# relay-set-d-decode.net
KiCad netlist of a schematic drawn in EAGLE
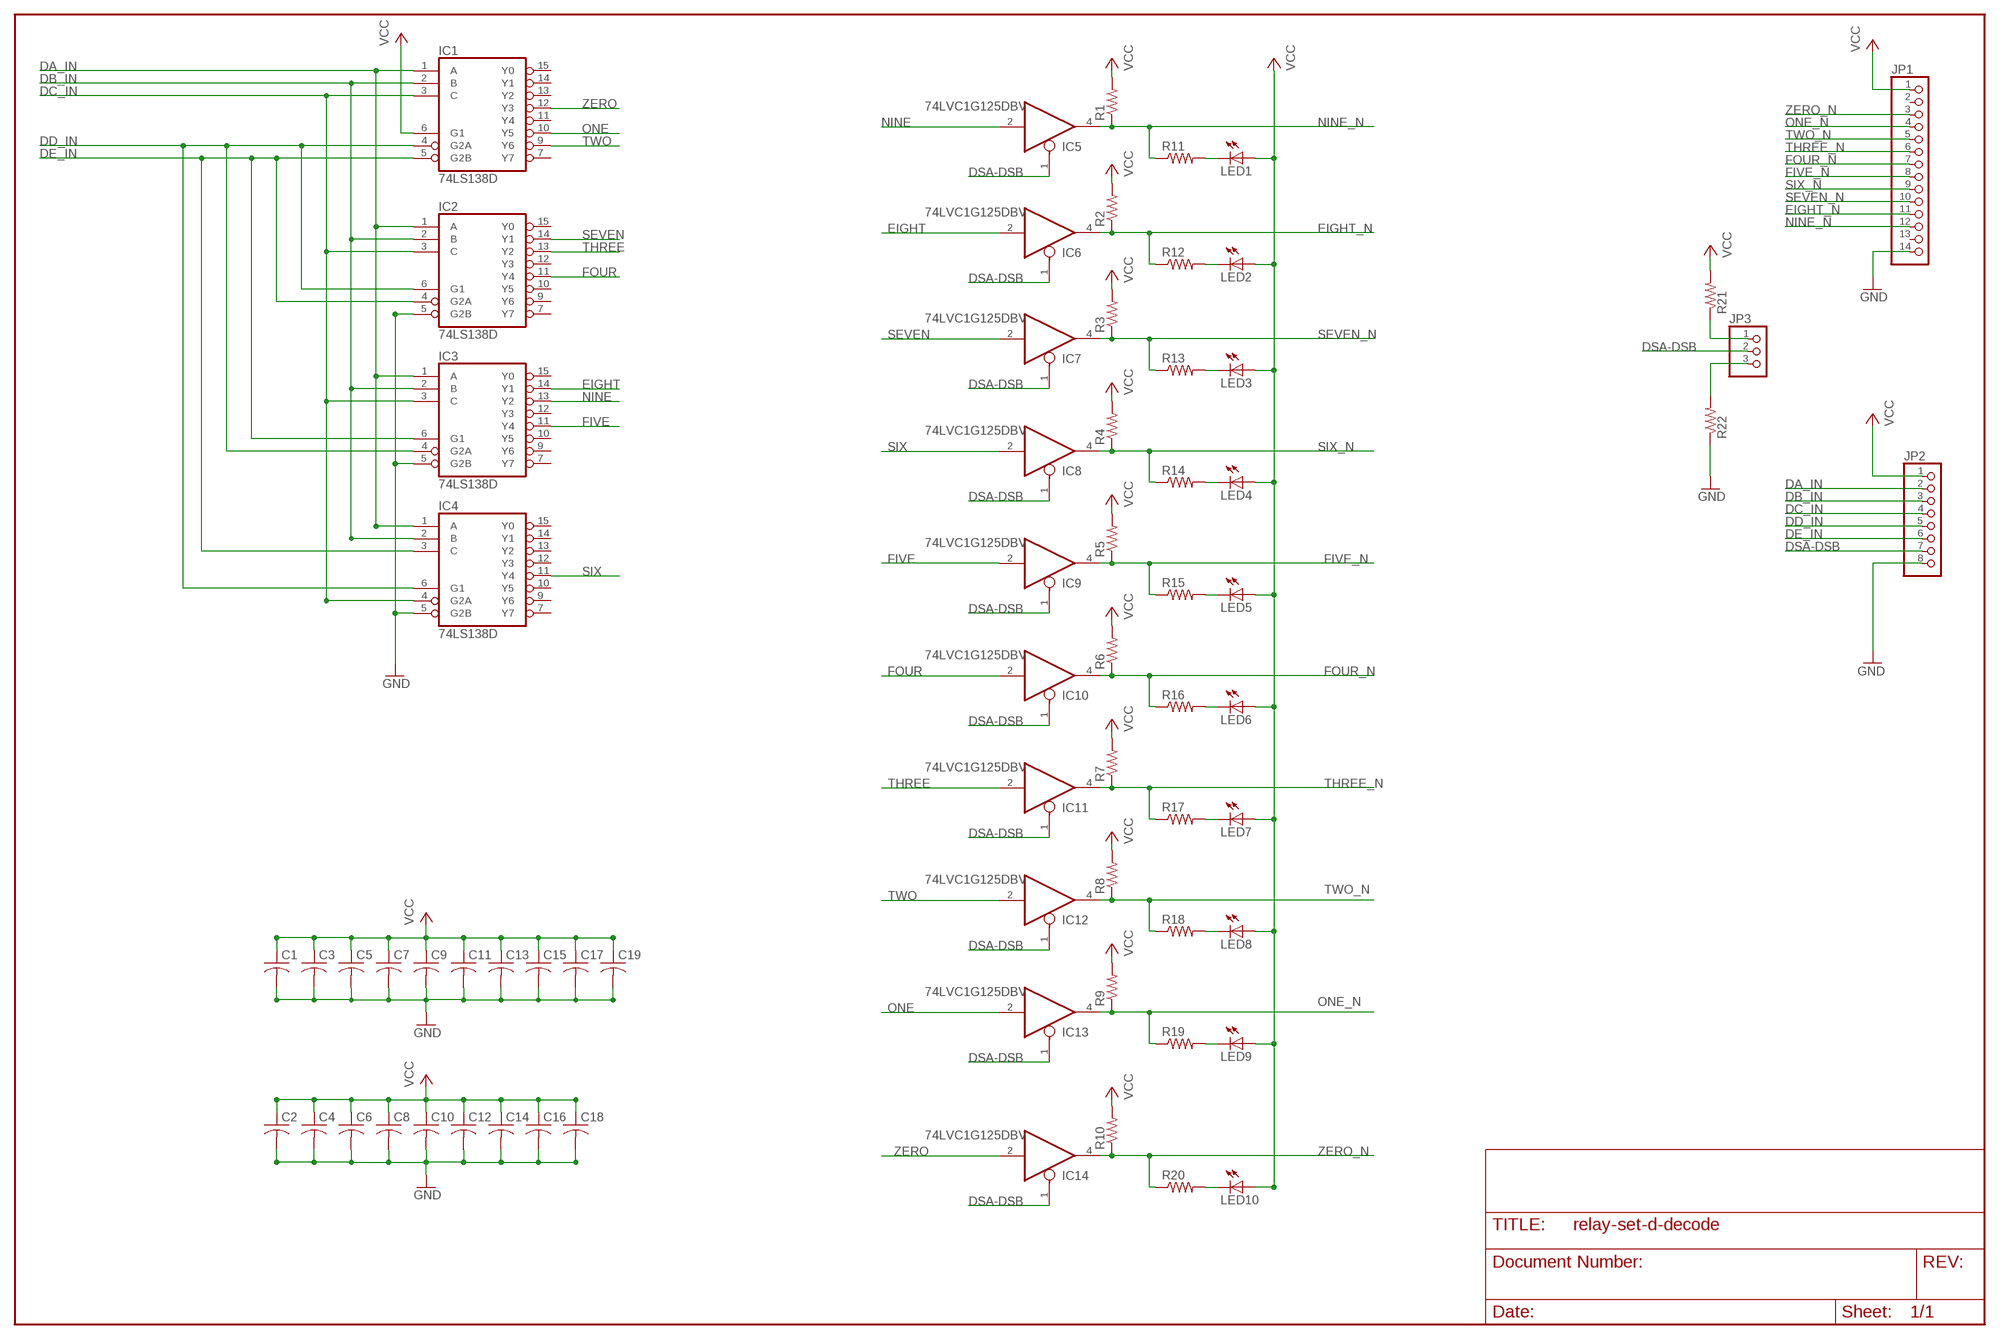
[diagram p0: schematic, sheet 1]

(export (version "E")
  (design (tool "Eeschema 10.0.6"))
  (components
    (comp (ref "C1")
      (value "C-USC0805")
      (footprint "eagle-import:C0805")
      (libsource (lib "eagle-import") (part "C-USC0805"))
    )
    (comp (ref "C2")
      (value "C-USC0805")
      (footprint "eagle-import:C0805")
      (libsource (lib "eagle-import") (part "C-USC0805"))
    )
    (comp (ref "C3")
      (value "C-USC0805")
      (footprint "eagle-import:C0805")
      (libsource (lib "eagle-import") (part "C-USC0805"))
    )
    (comp (ref "C4")
      (value "C-USC0805")
      (footprint "eagle-import:C0805")
      (libsource (lib "eagle-import") (part "C-USC0805"))
    )
    (comp (ref "C5")
      (value "C-USC0805")
      (footprint "eagle-import:C0805")
      (libsource (lib "eagle-import") (part "C-USC0805"))
    )
    (comp (ref "C6")
      (value "C-USC0805")
      (footprint "eagle-import:C0805")
      (libsource (lib "eagle-import") (part "C-USC0805"))
    )
    (comp (ref "C7")
      (value "C-USC0805")
      (footprint "eagle-import:C0805")
      (libsource (lib "eagle-import") (part "C-USC0805"))
    )
    (comp (ref "C8")
      (value "C-USC0805")
      (footprint "eagle-import:C0805")
      (libsource (lib "eagle-import") (part "C-USC0805"))
    )
    (comp (ref "C9")
      (value "C-USC0805")
      (footprint "eagle-import:C0805")
      (libsource (lib "eagle-import") (part "C-USC0805"))
    )
    (comp (ref "C10")
      (value "C-USC0805")
      (footprint "eagle-import:C0805")
      (libsource (lib "eagle-import") (part "C-USC0805"))
    )
    (comp (ref "C11")
      (value "C-USC0805")
      (footprint "eagle-import:C0805")
      (libsource (lib "eagle-import") (part "C-USC0805"))
    )
    (comp (ref "C12")
      (value "C-USC0805")
      (footprint "eagle-import:C0805")
      (libsource (lib "eagle-import") (part "C-USC0805"))
    )
    (comp (ref "C13")
      (value "C-USC0805")
      (footprint "eagle-import:C0805")
      (libsource (lib "eagle-import") (part "C-USC0805"))
    )
    (comp (ref "C14")
      (value "C-USC0805")
      (footprint "eagle-import:C0805")
      (libsource (lib "eagle-import") (part "C-USC0805"))
    )
    (comp (ref "C15")
      (value "C-USC0805")
      (footprint "eagle-import:C0805")
      (libsource (lib "eagle-import") (part "C-USC0805"))
    )
    (comp (ref "C16")
      (value "C-USC0805")
      (footprint "eagle-import:C0805")
      (libsource (lib "eagle-import") (part "C-USC0805"))
    )
    (comp (ref "C17")
      (value "C-USC0805")
      (footprint "eagle-import:C0805")
      (libsource (lib "eagle-import") (part "C-USC0805"))
    )
    (comp (ref "C18")
      (value "C-USC0805")
      (footprint "eagle-import:C0805")
      (libsource (lib "eagle-import") (part "C-USC0805"))
    )
    (comp (ref "C19")
      (value "C-USC0805")
      (footprint "eagle-import:C0805")
      (libsource (lib "eagle-import") (part "C-USC0805"))
    )
    (comp (ref "IC1")
      (value "74LS138D")
      (footprint "eagle-import:SO16")
      (libsource (lib "eagle-import") (part "74138DLS"))
    )
    (comp (ref "IC2")
      (value "74LS138D")
      (footprint "eagle-import:SO16")
      (libsource (lib "eagle-import") (part "74138DLS"))
    )
    (comp (ref "IC3")
      (value "74LS138D")
      (footprint "eagle-import:SO16")
      (libsource (lib "eagle-import") (part "74138DLS"))
    )
    (comp (ref "IC4")
      (value "74LS138D")
      (footprint "eagle-import:SO16")
      (libsource (lib "eagle-import") (part "74138DLS"))
    )
    (comp (ref "IC5")
      (value "74LVC1G125DBV")
      (footprint "eagle-import:SOT23-5")
      (libsource (lib "eagle-import") (part "741G125DBVLVC"))
    )
    (comp (ref "IC6")
      (value "74LVC1G125DBV")
      (footprint "eagle-import:SOT23-5")
      (libsource (lib "eagle-import") (part "741G125DBVLVC"))
    )
    (comp (ref "IC7")
      (value "74LVC1G125DBV")
      (footprint "eagle-import:SOT23-5")
      (libsource (lib "eagle-import") (part "741G125DBVLVC"))
    )
    (comp (ref "IC8")
      (value "74LVC1G125DBV")
      (footprint "eagle-import:SOT23-5")
      (libsource (lib "eagle-import") (part "741G125DBVLVC"))
    )
    (comp (ref "IC9")
      (value "74LVC1G125DBV")
      (footprint "eagle-import:SOT23-5")
      (libsource (lib "eagle-import") (part "741G125DBVLVC"))
    )
    (comp (ref "IC10")
      (value "74LVC1G125DBV")
      (footprint "eagle-import:SOT23-5")
      (libsource (lib "eagle-import") (part "741G125DBVLVC"))
    )
    (comp (ref "IC11")
      (value "74LVC1G125DBV")
      (footprint "eagle-import:SOT23-5")
      (libsource (lib "eagle-import") (part "741G125DBVLVC"))
    )
    (comp (ref "IC12")
      (value "74LVC1G125DBV")
      (footprint "eagle-import:SOT23-5")
      (libsource (lib "eagle-import") (part "741G125DBVLVC"))
    )
    (comp (ref "IC13")
      (value "74LVC1G125DBV")
      (footprint "eagle-import:SOT23-5")
      (libsource (lib "eagle-import") (part "741G125DBVLVC"))
    )
    (comp (ref "IC14")
      (value "74LVC1G125DBV")
      (footprint "eagle-import:SOT23-5")
      (libsource (lib "eagle-import") (part "741G125DBVLVC"))
    )
    (comp (ref "JP1")
      (value "PINHD-1X14")
      (footprint "eagle-import:1X14")
      (libsource (lib "eagle-import") (part "PINHD-1X14"))
    )
    (comp (ref "JP2")
      (value "PINHD-1X8")
      (footprint "eagle-import:1X08")
      (libsource (lib "eagle-import") (part "PINHD-1X8"))
    )
    (comp (ref "JP3")
      (value "PINHD-1X3")
      (footprint "eagle-import:1X03")
      (libsource (lib "eagle-import") (part "PINHD-1X3"))
    )
    (comp (ref "LED1")
      (value "LEDCHIP-LED0805")
      (footprint "eagle-import:CHIP-LED0805")
      (libsource (lib "eagle-import") (part "LEDCHIP-LED0805"))
    )
    (comp (ref "LED2")
      (value "LEDCHIP-LED0805")
      (footprint "eagle-import:CHIP-LED0805")
      (libsource (lib "eagle-import") (part "LEDCHIP-LED0805"))
    )
    (comp (ref "LED3")
      (value "LEDCHIP-LED0805")
      (footprint "eagle-import:CHIP-LED0805")
      (libsource (lib "eagle-import") (part "LEDCHIP-LED0805"))
    )
    (comp (ref "LED4")
      (value "LEDCHIP-LED0805")
      (footprint "eagle-import:CHIP-LED0805")
      (libsource (lib "eagle-import") (part "LEDCHIP-LED0805"))
    )
    (comp (ref "LED5")
      (value "LEDCHIP-LED0805")
      (footprint "eagle-import:CHIP-LED0805")
      (libsource (lib "eagle-import") (part "LEDCHIP-LED0805"))
    )
    (comp (ref "LED6")
      (value "LEDCHIP-LED0805")
      (footprint "eagle-import:CHIP-LED0805")
      (libsource (lib "eagle-import") (part "LEDCHIP-LED0805"))
    )
    (comp (ref "LED7")
      (value "LEDCHIP-LED0805")
      (footprint "eagle-import:CHIP-LED0805")
      (libsource (lib "eagle-import") (part "LEDCHIP-LED0805"))
    )
    (comp (ref "LED8")
      (value "LEDCHIP-LED0805")
      (footprint "eagle-import:CHIP-LED0805")
      (libsource (lib "eagle-import") (part "LEDCHIP-LED0805"))
    )
    (comp (ref "LED9")
      (value "LEDCHIP-LED0805")
      (footprint "eagle-import:CHIP-LED0805")
      (libsource (lib "eagle-import") (part "LEDCHIP-LED0805"))
    )
    (comp (ref "LED10")
      (value "LEDCHIP-LED0805")
      (footprint "eagle-import:CHIP-LED0805")
      (libsource (lib "eagle-import") (part "LEDCHIP-LED0805"))
    )
    (comp (ref "R1")
      (value "R-US_R0805")
      (footprint "eagle-import:R0805")
      (libsource (lib "eagle-import") (part "R-US_R0805"))
    )
    (comp (ref "R2")
      (value "R-US_R0805")
      (footprint "eagle-import:R0805")
      (libsource (lib "eagle-import") (part "R-US_R0805"))
    )
    (comp (ref "R3")
      (value "R-US_R0805")
      (footprint "eagle-import:R0805")
      (libsource (lib "eagle-import") (part "R-US_R0805"))
    )
    (comp (ref "R4")
      (value "R-US_R0805")
      (footprint "eagle-import:R0805")
      (libsource (lib "eagle-import") (part "R-US_R0805"))
    )
    (comp (ref "R5")
      (value "R-US_R0805")
      (footprint "eagle-import:R0805")
      (libsource (lib "eagle-import") (part "R-US_R0805"))
    )
    (comp (ref "R6")
      (value "R-US_R0805")
      (footprint "eagle-import:R0805")
      (libsource (lib "eagle-import") (part "R-US_R0805"))
    )
    (comp (ref "R7")
      (value "R-US_R0805")
      (footprint "eagle-import:R0805")
      (libsource (lib "eagle-import") (part "R-US_R0805"))
    )
    (comp (ref "R8")
      (value "R-US_R0805")
      (footprint "eagle-import:R0805")
      (libsource (lib "eagle-import") (part "R-US_R0805"))
    )
    (comp (ref "R9")
      (value "R-US_R0805")
      (footprint "eagle-import:R0805")
      (libsource (lib "eagle-import") (part "R-US_R0805"))
    )
    (comp (ref "R10")
      (value "R-US_R0805")
      (footprint "eagle-import:R0805")
      (libsource (lib "eagle-import") (part "R-US_R0805"))
    )
    (comp (ref "R11")
      (value "R-US_R0805")
      (footprint "eagle-import:R0805")
      (libsource (lib "eagle-import") (part "R-US_R0805"))
    )
    (comp (ref "R12")
      (value "R-US_R0805")
      (footprint "eagle-import:R0805")
      (libsource (lib "eagle-import") (part "R-US_R0805"))
    )
    (comp (ref "R13")
      (value "R-US_R0805")
      (footprint "eagle-import:R0805")
      (libsource (lib "eagle-import") (part "R-US_R0805"))
    )
    (comp (ref "R14")
      (value "R-US_R0805")
      (footprint "eagle-import:R0805")
      (libsource (lib "eagle-import") (part "R-US_R0805"))
    )
    (comp (ref "R15")
      (value "R-US_R0805")
      (footprint "eagle-import:R0805")
      (libsource (lib "eagle-import") (part "R-US_R0805"))
    )
    (comp (ref "R16")
      (value "R-US_R0805")
      (footprint "eagle-import:R0805")
      (libsource (lib "eagle-import") (part "R-US_R0805"))
    )
    (comp (ref "R17")
      (value "R-US_R0805")
      (footprint "eagle-import:R0805")
      (libsource (lib "eagle-import") (part "R-US_R0805"))
    )
    (comp (ref "R18")
      (value "R-US_R0805")
      (footprint "eagle-import:R0805")
      (libsource (lib "eagle-import") (part "R-US_R0805"))
    )
    (comp (ref "R19")
      (value "R-US_R0805")
      (footprint "eagle-import:R0805")
      (libsource (lib "eagle-import") (part "R-US_R0805"))
    )
    (comp (ref "R20")
      (value "R-US_R0805")
      (footprint "eagle-import:R0805")
      (libsource (lib "eagle-import") (part "R-US_R0805"))
    )
    (comp (ref "R21")
      (value "R-US_R0805")
      (footprint "eagle-import:R0805")
      (libsource (lib "eagle-import") (part "R-US_R0805"))
    )
    (comp (ref "R22")
      (value "R-US_R0805")
      (footprint "eagle-import:R0805")
      (libsource (lib "eagle-import") (part "R-US_R0805"))
    )
  )
  (nets
    (net (code "1") (name "/DA_IN") (class "Default")
      (node (ref "IC1") (pin "1") (pinfunction "A_1") (pintype "input"))
      (node (ref "IC2") (pin "1") (pinfunction "A_1") (pintype "input"))
      (node (ref "IC3") (pin "1") (pinfunction "A_1") (pintype "input"))
      (node (ref "IC4") (pin "1") (pinfunction "A_1") (pintype "input"))
      (node (ref "JP2") (pin "2") (pinfunction "2_2") (pintype "passive"))
    )
    (net (code "2") (name "/DB_IN") (class "Default")
      (node (ref "IC1") (pin "2") (pinfunction "B_2") (pintype "input"))
      (node (ref "IC2") (pin "2") (pinfunction "B_2") (pintype "input"))
      (node (ref "IC3") (pin "2") (pinfunction "B_2") (pintype "input"))
      (node (ref "IC4") (pin "2") (pinfunction "B_2") (pintype "input"))
      (node (ref "JP2") (pin "3") (pinfunction "3_3") (pintype "passive"))
    )
    (net (code "3") (name "/DC_IN") (class "Default")
      (node (ref "IC1") (pin "3") (pinfunction "C_3") (pintype "input"))
      (node (ref "IC2") (pin "3") (pinfunction "C_3") (pintype "input"))
      (node (ref "IC3") (pin "3") (pinfunction "C_3") (pintype "input"))
      (node (ref "IC4") (pin "4") (pinfunction "G2A_4") (pintype "input"))
      (node (ref "JP2") (pin "4") (pinfunction "4_4") (pintype "passive"))
    )
    (net (code "4") (name "/DD_IN") (class "Default")
      (node (ref "IC1") (pin "4") (pinfunction "G2A_4") (pintype "input"))
      (node (ref "IC2") (pin "6") (pinfunction "G1_6") (pintype "input"))
      (node (ref "IC3") (pin "4") (pinfunction "G2A_4") (pintype "input"))
      (node (ref "IC4") (pin "6") (pinfunction "G1_6") (pintype "input"))
      (node (ref "JP2") (pin "5") (pinfunction "5_5") (pintype "passive"))
    )
    (net (code "5") (name "/DE_IN") (class "Default")
      (node (ref "IC1") (pin "5") (pinfunction "G2B_5") (pintype "input"))
      (node (ref "IC2") (pin "4") (pinfunction "G2A_4") (pintype "input"))
      (node (ref "IC3") (pin "6") (pinfunction "G1_6") (pintype "input"))
      (node (ref "IC4") (pin "3") (pinfunction "C_3") (pintype "input"))
      (node (ref "JP2") (pin "6") (pinfunction "6_6") (pintype "passive"))
    )
    (net (code "6") (name "/DSA-DSB") (class "Default")
      (node (ref "IC10") (pin "1") (pinfunction "OE_1") (pintype "input"))
      (node (ref "IC11") (pin "1") (pinfunction "OE_1") (pintype "input"))
      (node (ref "IC12") (pin "1") (pinfunction "OE_1") (pintype "input"))
      (node (ref "IC13") (pin "1") (pinfunction "OE_1") (pintype "input"))
      (node (ref "IC14") (pin "1") (pinfunction "OE_1") (pintype "input"))
      (node (ref "IC5") (pin "1") (pinfunction "OE_1") (pintype "input"))
      (node (ref "IC6") (pin "1") (pinfunction "OE_1") (pintype "input"))
      (node (ref "IC7") (pin "1") (pinfunction "OE_1") (pintype "input"))
      (node (ref "IC8") (pin "1") (pinfunction "OE_1") (pintype "input"))
      (node (ref "IC9") (pin "1") (pinfunction "OE_1") (pintype "input"))
      (node (ref "JP2") (pin "7") (pinfunction "7_7") (pintype "passive"))
      (node (ref "JP3") (pin "2") (pinfunction "2_2") (pintype "passive"))
    )
    (net (code "7") (name "/EIGHT") (class "Default")
      (node (ref "IC3") (pin "14") (pinfunction "Y1_14") (pintype "output"))
      (node (ref "IC6") (pin "2") (pinfunction "I_2") (pintype "input"))
    )
    (net (code "8") (name "/EIGHT_N") (class "Default")
      (node (ref "IC6") (pin "4") (pinfunction "O_4") (pintype "tri_state"))
      (node (ref "JP1") (pin "11") (pinfunction "11_11") (pintype "passive"))
      (node (ref "R12") (pin "1") (pinfunction "1_1") (pintype "passive"))
      (node (ref "R2") (pin "1") (pinfunction "1_1") (pintype "passive"))
    )
    (net (code "9") (name "/FIVE") (class "Default")
      (node (ref "IC3") (pin "11") (pinfunction "Y4_11") (pintype "output"))
      (node (ref "IC9") (pin "2") (pinfunction "I_2") (pintype "input"))
    )
    (net (code "10") (name "/FIVE_N") (class "Default")
      (node (ref "IC9") (pin "4") (pinfunction "O_4") (pintype "tri_state"))
      (node (ref "JP1") (pin "8") (pinfunction "8_8") (pintype "passive"))
      (node (ref "R15") (pin "1") (pinfunction "1_1") (pintype "passive"))
      (node (ref "R5") (pin "1") (pinfunction "1_1") (pintype "passive"))
    )
    (net (code "11") (name "/FOUR") (class "Default")
      (node (ref "IC10") (pin "2") (pinfunction "I_2") (pintype "input"))
      (node (ref "IC2") (pin "11") (pinfunction "Y4_11") (pintype "output"))
    )
    (net (code "12") (name "/FOUR_N") (class "Default")
      (node (ref "IC10") (pin "4") (pinfunction "O_4") (pintype "tri_state"))
      (node (ref "JP1") (pin "7") (pinfunction "7_7") (pintype "passive"))
      (node (ref "R16") (pin "1") (pinfunction "1_1") (pintype "passive"))
      (node (ref "R6") (pin "1") (pinfunction "1_1") (pintype "passive"))
    )
    (net (code "13") (name "/NINE") (class "Default")
      (node (ref "IC3") (pin "13") (pinfunction "Y2_13") (pintype "output"))
      (node (ref "IC5") (pin "2") (pinfunction "I_2") (pintype "input"))
    )
    (net (code "14") (name "/NINE_N") (class "Default")
      (node (ref "IC5") (pin "4") (pinfunction "O_4") (pintype "tri_state"))
      (node (ref "JP1") (pin "12") (pinfunction "12_12") (pintype "passive"))
      (node (ref "R1") (pin "1") (pinfunction "1_1") (pintype "passive"))
      (node (ref "R11") (pin "1") (pinfunction "1_1") (pintype "passive"))
    )
    (net (code "15") (name "/ONE") (class "Default")
      (node (ref "IC1") (pin "10") (pinfunction "Y5_10") (pintype "output"))
      (node (ref "IC13") (pin "2") (pinfunction "I_2") (pintype "input"))
    )
    (net (code "16") (name "/ONE_N") (class "Default")
      (node (ref "IC13") (pin "4") (pinfunction "O_4") (pintype "tri_state"))
      (node (ref "JP1") (pin "4") (pinfunction "4_4") (pintype "passive"))
      (node (ref "R19") (pin "1") (pinfunction "1_1") (pintype "passive"))
      (node (ref "R9") (pin "1") (pinfunction "1_1") (pintype "passive"))
    )
    (net (code "17") (name "/SEVEN") (class "Default")
      (node (ref "IC2") (pin "14") (pinfunction "Y1_14") (pintype "output"))
      (node (ref "IC7") (pin "2") (pinfunction "I_2") (pintype "input"))
    )
    (net (code "18") (name "/SEVEN_N") (class "Default")
      (node (ref "IC7") (pin "4") (pinfunction "O_4") (pintype "tri_state"))
      (node (ref "JP1") (pin "10") (pinfunction "10_10") (pintype "passive"))
      (node (ref "R13") (pin "1") (pinfunction "1_1") (pintype "passive"))
      (node (ref "R3") (pin "1") (pinfunction "1_1") (pintype "passive"))
    )
    (net (code "19") (name "/SIX") (class "Default")
      (node (ref "IC4") (pin "11") (pinfunction "Y4_11") (pintype "output"))
      (node (ref "IC8") (pin "2") (pinfunction "I_2") (pintype "input"))
    )
    (net (code "20") (name "/SIX_N") (class "Default")
      (node (ref "IC8") (pin "4") (pinfunction "O_4") (pintype "tri_state"))
      (node (ref "JP1") (pin "9") (pinfunction "9_9") (pintype "passive"))
      (node (ref "R14") (pin "1") (pinfunction "1_1") (pintype "passive"))
      (node (ref "R4") (pin "1") (pinfunction "1_1") (pintype "passive"))
    )
    (net (code "21") (name "/THREE") (class "Default")
      (node (ref "IC11") (pin "2") (pinfunction "I_2") (pintype "input"))
      (node (ref "IC2") (pin "13") (pinfunction "Y2_13") (pintype "output"))
    )
    (net (code "22") (name "/THREE_N") (class "Default")
      (node (ref "IC11") (pin "4") (pinfunction "O_4") (pintype "tri_state"))
      (node (ref "JP1") (pin "6") (pinfunction "6_6") (pintype "passive"))
      (node (ref "R17") (pin "1") (pinfunction "1_1") (pintype "passive"))
      (node (ref "R7") (pin "1") (pinfunction "1_1") (pintype "passive"))
    )
    (net (code "23") (name "/TWO") (class "Default")
      (node (ref "IC1") (pin "9") (pinfunction "Y6_9") (pintype "output"))
      (node (ref "IC12") (pin "2") (pinfunction "I_2") (pintype "input"))
    )
    (net (code "24") (name "/TWO_N") (class "Default")
      (node (ref "IC12") (pin "4") (pinfunction "O_4") (pintype "tri_state"))
      (node (ref "JP1") (pin "5") (pinfunction "5_5") (pintype "passive"))
      (node (ref "R18") (pin "1") (pinfunction "1_1") (pintype "passive"))
      (node (ref "R8") (pin "1") (pinfunction "1_1") (pintype "passive"))
    )
    (net (code "25") (name "/ZERO") (class "Default")
      (node (ref "IC1") (pin "12") (pinfunction "Y3_12") (pintype "output"))
      (node (ref "IC14") (pin "2") (pinfunction "I_2") (pintype "input"))
    )
    (net (code "26") (name "/ZERO_N") (class "Default")
      (node (ref "IC14") (pin "4") (pinfunction "O_4") (pintype "tri_state"))
      (node (ref "JP1") (pin "3") (pinfunction "3_3") (pintype "passive"))
      (node (ref "R10") (pin "1") (pinfunction "1_1") (pintype "passive"))
      (node (ref "R20") (pin "1") (pinfunction "1_1") (pintype "passive"))
    )
    (net (code "27") (name "GND") (class "Default")
      (node (ref "C1") (pin "2") (pinfunction "2_2") (pintype "passive"))
      (node (ref "C10") (pin "2") (pinfunction "2_2") (pintype "passive"))
      (node (ref "C11") (pin "2") (pinfunction "2_2") (pintype "passive"))
      (node (ref "C12") (pin "2") (pinfunction "2_2") (pintype "passive"))
      (node (ref "C13") (pin "2") (pinfunction "2_2") (pintype "passive"))
      (node (ref "C14") (pin "2") (pinfunction "2_2") (pintype "passive"))
      (node (ref "C15") (pin "2") (pinfunction "2_2") (pintype "passive"))
      (node (ref "C16") (pin "2") (pinfunction "2_2") (pintype "passive"))
      (node (ref "C17") (pin "2") (pinfunction "2_2") (pintype "passive"))
      (node (ref "C18") (pin "2") (pinfunction "2_2") (pintype "passive"))
      (node (ref "C19") (pin "2") (pinfunction "2_2") (pintype "passive"))
      (node (ref "C2") (pin "2") (pinfunction "2_2") (pintype "passive"))
      (node (ref "C3") (pin "2") (pinfunction "2_2") (pintype "passive"))
      (node (ref "C4") (pin "2") (pinfunction "2_2") (pintype "passive"))
      (node (ref "C5") (pin "2") (pinfunction "2_2") (pintype "passive"))
      (node (ref "C6") (pin "2") (pinfunction "2_2") (pintype "passive"))
      (node (ref "C7") (pin "2") (pinfunction "2_2") (pintype "passive"))
      (node (ref "C8") (pin "2") (pinfunction "2_2") (pintype "passive"))
      (node (ref "C9") (pin "2") (pinfunction "2_2") (pintype "passive"))
      (node (ref "IC2") (pin "5") (pinfunction "G2B_5") (pintype "input"))
      (node (ref "IC3") (pin "5") (pinfunction "G2B_5") (pintype "input"))
      (node (ref "IC4") (pin "5") (pinfunction "G2B_5") (pintype "input"))
      (node (ref "JP1") (pin "14") (pinfunction "14_14") (pintype "passive"))
      (node (ref "JP2") (pin "8") (pinfunction "8_8") (pintype "passive"))
      (node (ref "R22") (pin "1") (pinfunction "1_1") (pintype "passive"))
    )
    (net (code "28") (name "Net-(JP3-Pad1)") (class "Default")
      (node (ref "JP3") (pin "1") (pinfunction "1_1") (pintype "passive"))
      (node (ref "R21") (pin "1") (pinfunction "1_1") (pintype "passive"))
    )
    (net (code "29") (name "Net-(JP3-Pad3)") (class "Default")
      (node (ref "JP3") (pin "3") (pinfunction "3_3") (pintype "passive"))
      (node (ref "R22") (pin "2") (pinfunction "2_2") (pintype "passive"))
    )
    (net (code "30") (name "Net-(LED1-PadC)") (class "Default")
      (node (ref "LED1") (pin "C") (pinfunction "C_C") (pintype "passive"))
      (node (ref "R11") (pin "2") (pinfunction "2_2") (pintype "passive"))
    )
    (net (code "31") (name "Net-(LED2-PadC)") (class "Default")
      (node (ref "LED2") (pin "C") (pinfunction "C_C") (pintype "passive"))
      (node (ref "R12") (pin "2") (pinfunction "2_2") (pintype "passive"))
    )
    (net (code "32") (name "Net-(LED3-PadC)") (class "Default")
      (node (ref "LED3") (pin "C") (pinfunction "C_C") (pintype "passive"))
      (node (ref "R13") (pin "2") (pinfunction "2_2") (pintype "passive"))
    )
    (net (code "33") (name "Net-(LED4-PadC)") (class "Default")
      (node (ref "LED4") (pin "C") (pinfunction "C_C") (pintype "passive"))
      (node (ref "R14") (pin "2") (pinfunction "2_2") (pintype "passive"))
    )
    (net (code "34") (name "Net-(LED5-PadC)") (class "Default")
      (node (ref "LED5") (pin "C") (pinfunction "C_C") (pintype "passive"))
      (node (ref "R15") (pin "2") (pinfunction "2_2") (pintype "passive"))
    )
    (net (code "35") (name "Net-(LED6-PadC)") (class "Default")
      (node (ref "LED6") (pin "C") (pinfunction "C_C") (pintype "passive"))
      (node (ref "R16") (pin "2") (pinfunction "2_2") (pintype "passive"))
    )
    (net (code "36") (name "Net-(LED7-PadC)") (class "Default")
      (node (ref "LED7") (pin "C") (pinfunction "C_C") (pintype "passive"))
      (node (ref "R17") (pin "2") (pinfunction "2_2") (pintype "passive"))
    )
    (net (code "37") (name "Net-(LED8-PadC)") (class "Default")
      (node (ref "LED8") (pin "C") (pinfunction "C_C") (pintype "passive"))
      (node (ref "R18") (pin "2") (pinfunction "2_2") (pintype "passive"))
    )
    (net (code "38") (name "Net-(LED9-PadC)") (class "Default")
      (node (ref "LED9") (pin "C") (pinfunction "C_C") (pintype "passive"))
      (node (ref "R19") (pin "2") (pinfunction "2_2") (pintype "passive"))
    )
    (net (code "39") (name "Net-(LED10-PadC)") (class "Default")
      (node (ref "LED10") (pin "C") (pinfunction "C_C") (pintype "passive"))
      (node (ref "R20") (pin "2") (pinfunction "2_2") (pintype "passive"))
    )
    (net (code "40") (name "VCC") (class "Default")
      (node (ref "C1") (pin "1") (pinfunction "1_1") (pintype "passive"))
      (node (ref "C10") (pin "1") (pinfunction "1_1") (pintype "passive"))
      (node (ref "C11") (pin "1") (pinfunction "1_1") (pintype "passive"))
      (node (ref "C12") (pin "1") (pinfunction "1_1") (pintype "passive"))
      (node (ref "C13") (pin "1") (pinfunction "1_1") (pintype "passive"))
      (node (ref "C14") (pin "1") (pinfunction "1_1") (pintype "passive"))
      (node (ref "C15") (pin "1") (pinfunction "1_1") (pintype "passive"))
      (node (ref "C16") (pin "1") (pinfunction "1_1") (pintype "passive"))
      (node (ref "C17") (pin "1") (pinfunction "1_1") (pintype "passive"))
      (node (ref "C18") (pin "1") (pinfunction "1_1") (pintype "passive"))
      (node (ref "C19") (pin "1") (pinfunction "1_1") (pintype "passive"))
      (node (ref "C2") (pin "1") (pinfunction "1_1") (pintype "passive"))
      (node (ref "C3") (pin "1") (pinfunction "1_1") (pintype "passive"))
      (node (ref "C4") (pin "1") (pinfunction "1_1") (pintype "passive"))
      (node (ref "C5") (pin "1") (pinfunction "1_1") (pintype "passive"))
      (node (ref "C6") (pin "1") (pinfunction "1_1") (pintype "passive"))
      (node (ref "C7") (pin "1") (pinfunction "1_1") (pintype "passive"))
      (node (ref "C8") (pin "1") (pinfunction "1_1") (pintype "passive"))
      (node (ref "C9") (pin "1") (pinfunction "1_1") (pintype "passive"))
      (node (ref "IC1") (pin "6") (pinfunction "G1_6") (pintype "input"))
      (node (ref "JP1") (pin "1") (pinfunction "1_1") (pintype "passive"))
      (node (ref "JP2") (pin "1") (pinfunction "1_1") (pintype "passive"))
      (node (ref "LED1") (pin "A") (pinfunction "A_A") (pintype "passive"))
      (node (ref "LED10") (pin "A") (pinfunction "A_A") (pintype "passive"))
      (node (ref "LED2") (pin "A") (pinfunction "A_A") (pintype "passive"))
      (node (ref "LED3") (pin "A") (pinfunction "A_A") (pintype "passive"))
      (node (ref "LED4") (pin "A") (pinfunction "A_A") (pintype "passive"))
      (node (ref "LED5") (pin "A") (pinfunction "A_A") (pintype "passive"))
      (node (ref "LED6") (pin "A") (pinfunction "A_A") (pintype "passive"))
      (node (ref "LED7") (pin "A") (pinfunction "A_A") (pintype "passive"))
      (node (ref "LED8") (pin "A") (pinfunction "A_A") (pintype "passive"))
      (node (ref "LED9") (pin "A") (pinfunction "A_A") (pintype "passive"))
      (node (ref "R1") (pin "2") (pinfunction "2_2") (pintype "passive"))
      (node (ref "R10") (pin "2") (pinfunction "2_2") (pintype "passive"))
      (node (ref "R2") (pin "2") (pinfunction "2_2") (pintype "passive"))
      (node (ref "R21") (pin "2") (pinfunction "2_2") (pintype "passive"))
      (node (ref "R3") (pin "2") (pinfunction "2_2") (pintype "passive"))
      (node (ref "R4") (pin "2") (pinfunction "2_2") (pintype "passive"))
      (node (ref "R5") (pin "2") (pinfunction "2_2") (pintype "passive"))
      (node (ref "R6") (pin "2") (pinfunction "2_2") (pintype "passive"))
      (node (ref "R7") (pin "2") (pinfunction "2_2") (pintype "passive"))
      (node (ref "R8") (pin "2") (pinfunction "2_2") (pintype "passive"))
      (node (ref "R9") (pin "2") (pinfunction "2_2") (pintype "passive"))
    )
    (net (code "41") (name "unconnected-(IC1A-Y0-Pad15)") (class "Default")
      (node (ref "IC1") (pin "15") (pinfunction "Y0_15") (pintype "output"))
    )
    (net (code "42") (name "unconnected-(IC1A-Y1-Pad14)") (class "Default")
      (node (ref "IC1") (pin "14") (pinfunction "Y1_14") (pintype "output"))
    )
    (net (code "43") (name "unconnected-(IC1A-Y2-Pad13)") (class "Default")
      (node (ref "IC1") (pin "13") (pinfunction "Y2_13") (pintype "output"))
    )
    (net (code "44") (name "unconnected-(IC1A-Y4-Pad11)") (class "Default")
      (node (ref "IC1") (pin "11") (pinfunction "Y4_11") (pintype "output"))
    )
    (net (code "45") (name "unconnected-(IC1A-Y7-Pad7)") (class "Default")
      (node (ref "IC1") (pin "7") (pinfunction "Y7_7") (pintype "output"))
    )
    (net (code "46") (name "unconnected-(IC2A-Y0-Pad15)") (class "Default")
      (node (ref "IC2") (pin "15") (pinfunction "Y0_15") (pintype "output"))
    )
    (net (code "47") (name "unconnected-(IC2A-Y3-Pad12)") (class "Default")
      (node (ref "IC2") (pin "12") (pinfunction "Y3_12") (pintype "output"))
    )
    (net (code "48") (name "unconnected-(IC2A-Y5-Pad10)") (class "Default")
      (node (ref "IC2") (pin "10") (pinfunction "Y5_10") (pintype "output"))
    )
    (net (code "49") (name "unconnected-(IC2A-Y6-Pad9)") (class "Default")
      (node (ref "IC2") (pin "9") (pinfunction "Y6_9") (pintype "output"))
    )
    (net (code "50") (name "unconnected-(IC2A-Y7-Pad7)") (class "Default")
      (node (ref "IC2") (pin "7") (pinfunction "Y7_7") (pintype "output"))
    )
    (net (code "51") (name "unconnected-(IC3A-Y0-Pad15)") (class "Default")
      (node (ref "IC3") (pin "15") (pinfunction "Y0_15") (pintype "output"))
    )
    (net (code "52") (name "unconnected-(IC3A-Y3-Pad12)") (class "Default")
      (node (ref "IC3") (pin "12") (pinfunction "Y3_12") (pintype "output"))
    )
    (net (code "53") (name "unconnected-(IC3A-Y5-Pad10)") (class "Default")
      (node (ref "IC3") (pin "10") (pinfunction "Y5_10") (pintype "output"))
    )
    (net (code "54") (name "unconnected-(IC3A-Y6-Pad9)") (class "Default")
      (node (ref "IC3") (pin "9") (pinfunction "Y6_9") (pintype "output"))
    )
    (net (code "55") (name "unconnected-(IC3A-Y7-Pad7)") (class "Default")
      (node (ref "IC3") (pin "7") (pinfunction "Y7_7") (pintype "output"))
    )
    (net (code "56") (name "unconnected-(IC4A-Y0-Pad15)") (class "Default")
      (node (ref "IC4") (pin "15") (pinfunction "Y0_15") (pintype "output"))
    )
    (net (code "57") (name "unconnected-(IC4A-Y1-Pad14)") (class "Default")
      (node (ref "IC4") (pin "14") (pinfunction "Y1_14") (pintype "output"))
    )
    (net (code "58") (name "unconnected-(IC4A-Y2-Pad13)") (class "Default")
      (node (ref "IC4") (pin "13") (pinfunction "Y2_13") (pintype "output"))
    )
    (net (code "59") (name "unconnected-(IC4A-Y3-Pad12)") (class "Default")
      (node (ref "IC4") (pin "12") (pinfunction "Y3_12") (pintype "output"))
    )
    (net (code "60") (name "unconnected-(IC4A-Y5-Pad10)") (class "Default")
      (node (ref "IC4") (pin "10") (pinfunction "Y5_10") (pintype "output"))
    )
    (net (code "61") (name "unconnected-(IC4A-Y6-Pad9)") (class "Default")
      (node (ref "IC4") (pin "9") (pinfunction "Y6_9") (pintype "output"))
    )
    (net (code "62") (name "unconnected-(IC4A-Y7-Pad7)") (class "Default")
      (node (ref "IC4") (pin "7") (pinfunction "Y7_7") (pintype "output"))
    )
    (net (code "63") (name "unconnected-(JP1-Pad2)") (class "Default")
      (node (ref "JP1") (pin "2") (pinfunction "2_2") (pintype "passive"))
    )
    (net (code "64") (name "unconnected-(JP1-Pad13)") (class "Default")
      (node (ref "JP1") (pin "13") (pinfunction "13_13") (pintype "passive"))
    )
  )
)
